# P07-LCD.net
KiCad netlist of a schematic drawn in Altium Designer
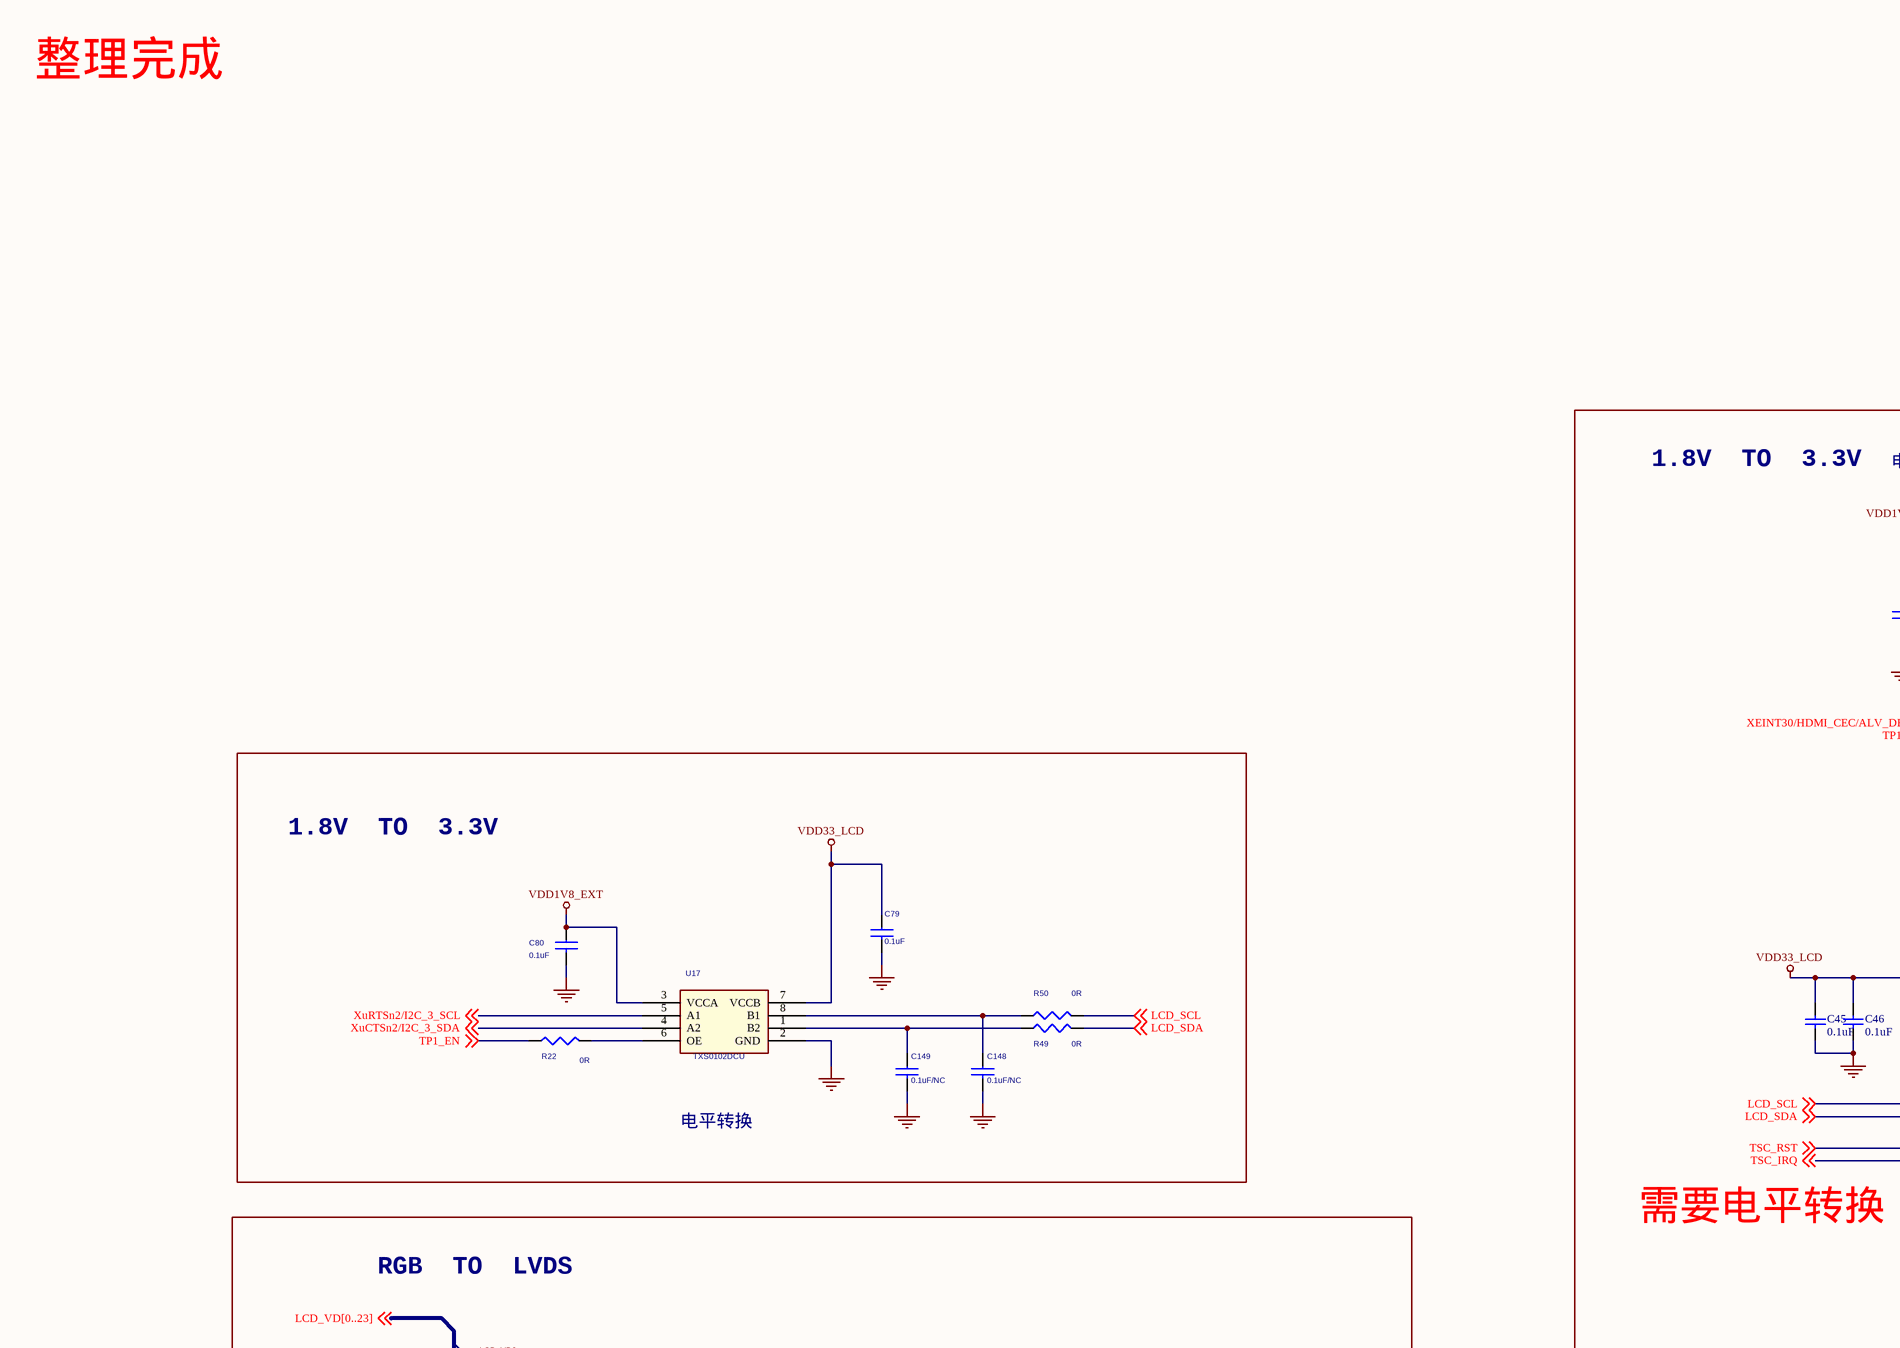
[diagram p0: P07-LCD.SchDoc, top left]
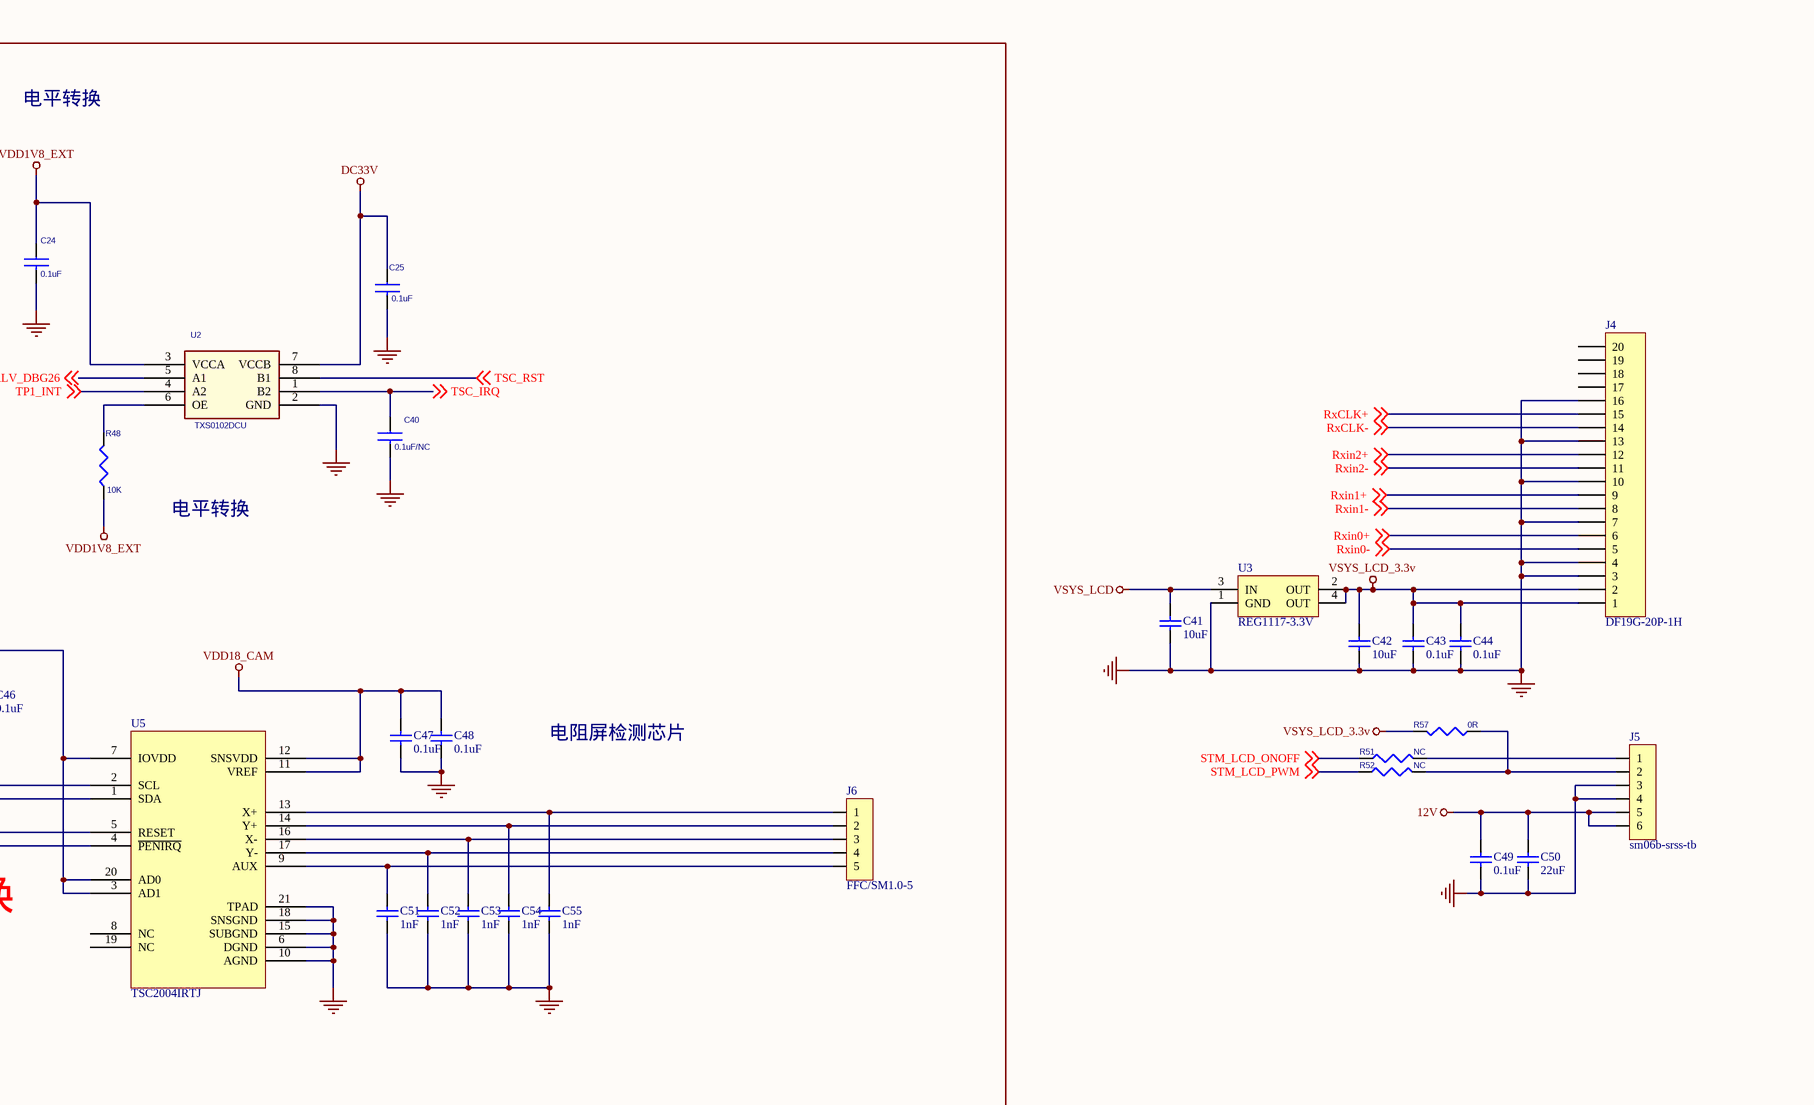
[diagram p1: P07-LCD.SchDoc, top right]
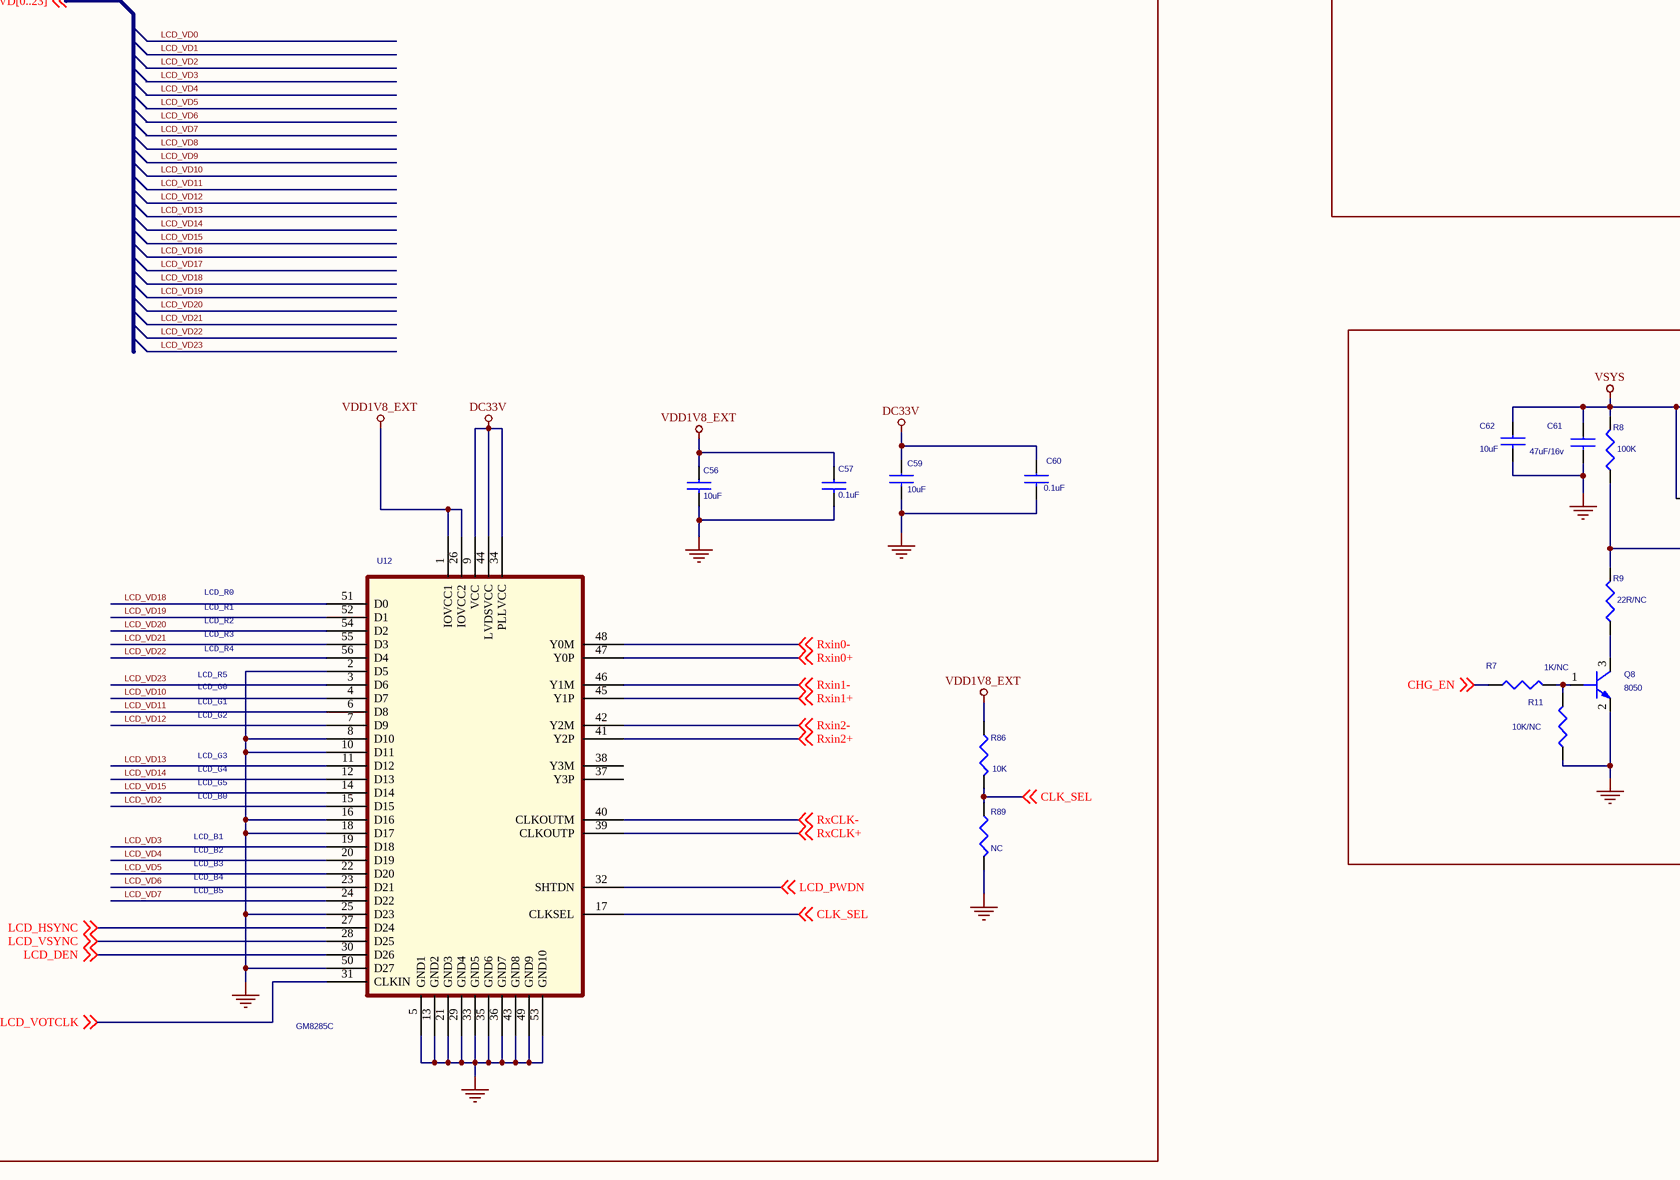
[diagram p2: P07-LCD.SchDoc, bottom left]
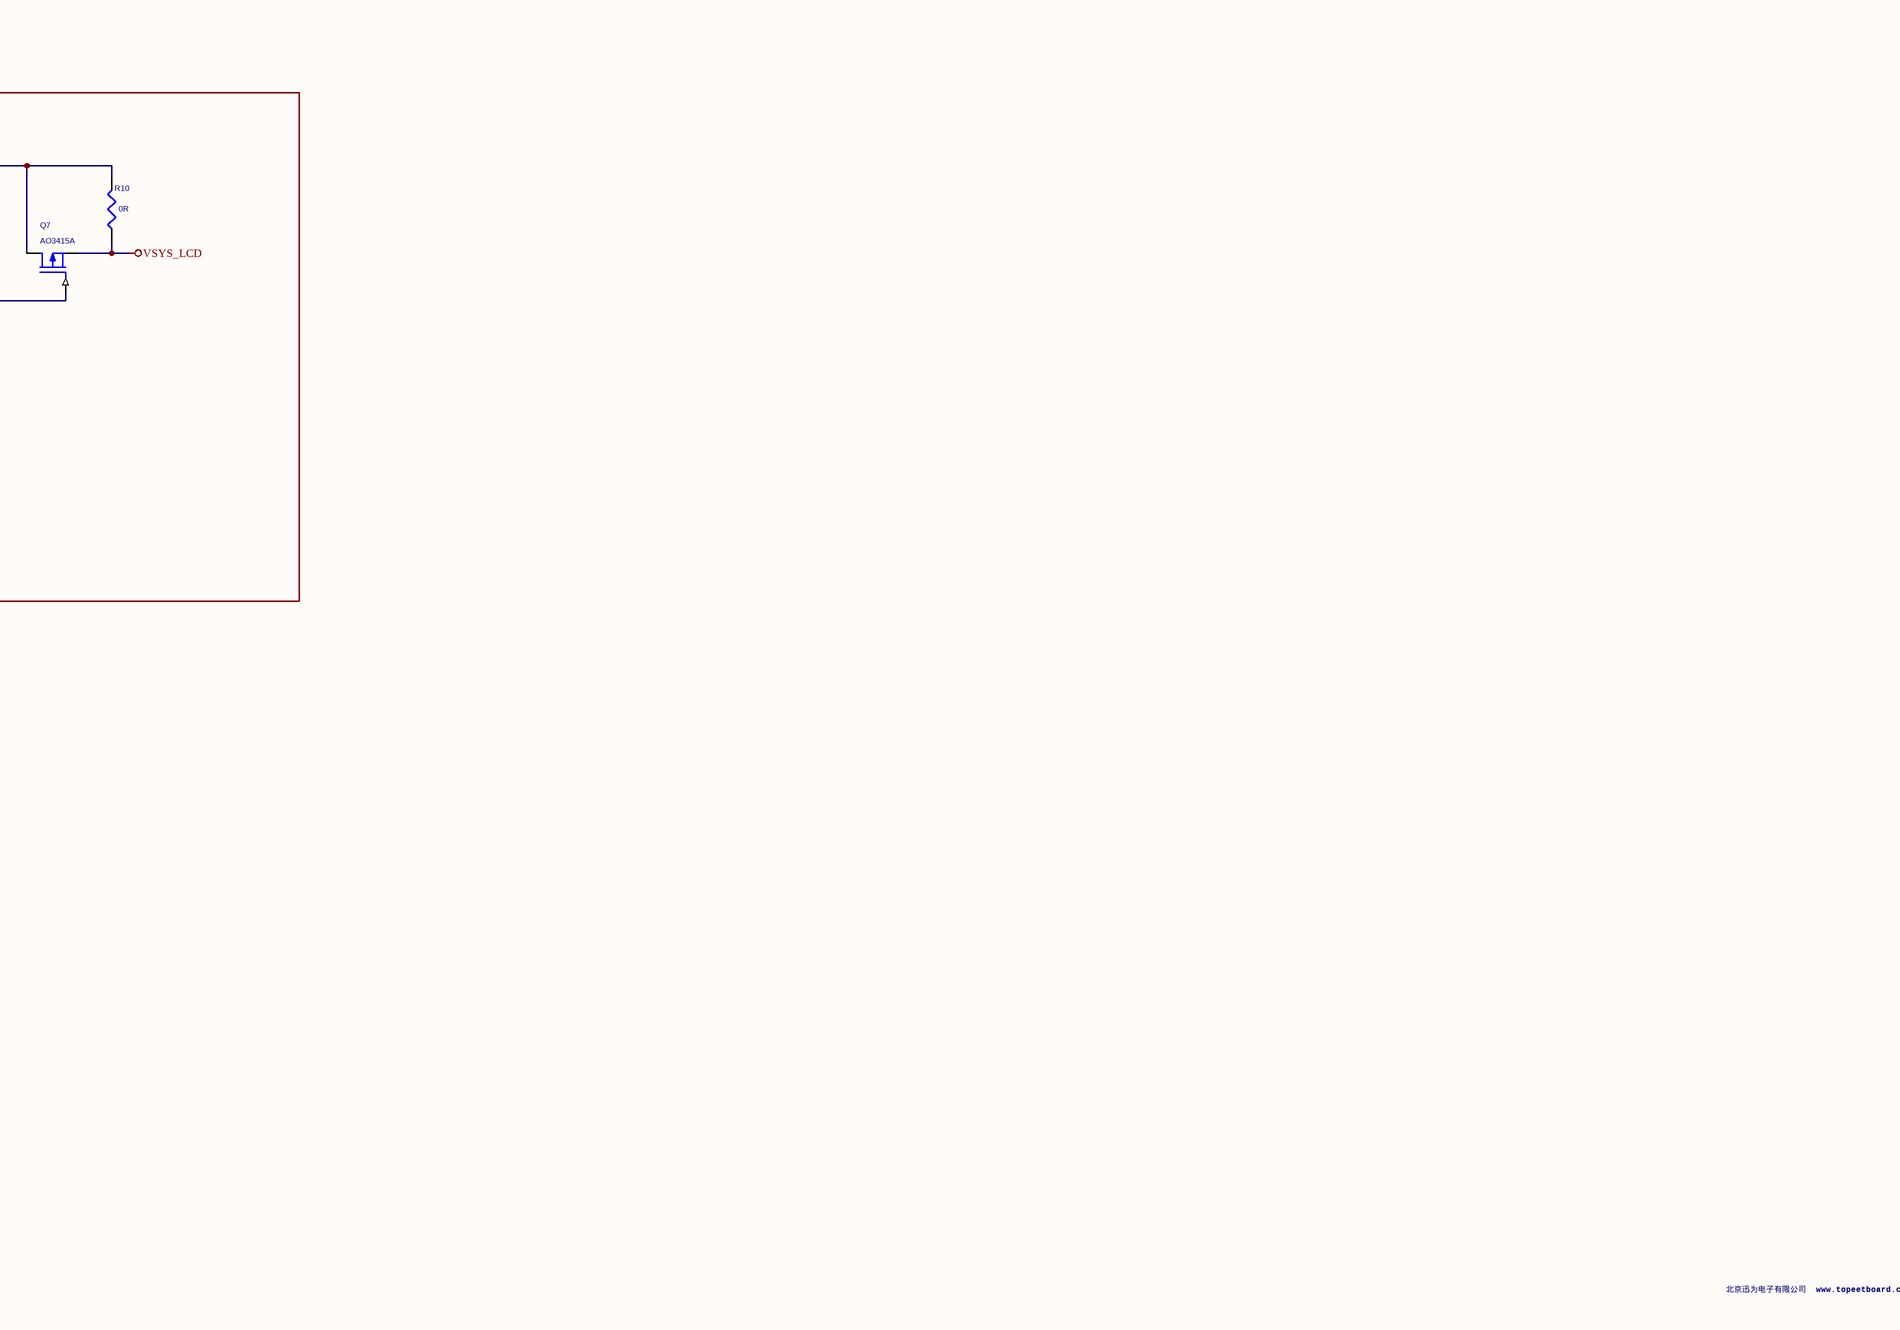
[diagram p3: P07-LCD.SchDoc, bottom right]

(export (version "E")
  (design (tool "Eeschema 10.0.6"))
  (components
    (comp (ref "C24") (value "0.1uF") (footprint "C0603-S") (libsource (lib "*") (part "C0603_0")))
    (comp (ref "C25") (value "0.1uF") (footprint "C0603-S") (libsource (lib "*") (part "C0603_0")))
    (comp (ref "C40") (value "0.1uF/NC") (footprint "C0603-S") (libsource (lib "*") (part "C0603_0")))
    (comp (ref "C41")
      (value "10uF")
      (footprint "C0603-s")
      (description "CAP")
      (fields (field (name "PUBLISHER") "Altium Limited"))
      (libsource (lib "Passive Components Class") (part "CAP"))
    )
    (comp (ref "C42")
      (value "10uF")
      (footprint "C0603-s")
      (description "CAP")
      (fields (field (name "PUBLISHER") "Altium Limited"))
      (libsource (lib "Passive Components Class") (part "CAP"))
    )
    (comp (ref "C43")
      (value "0.1uF")
      (footprint "C0603-s")
      (description "CAP")
      (fields (field (name "PUBLISHER") "Altium Limited"))
      (libsource (lib "Passive Components Class") (part "CAP"))
    )
    (comp (ref "C44")
      (value "0.1uF")
      (footprint "C0603-s")
      (description "CAP")
      (fields (field (name "PUBLISHER") "Altium Limited"))
      (libsource (lib "Passive Components Class") (part "CAP"))
    )
    (comp (ref "C45") (value "0.1uF") (footprint "C0603-S") (libsource (lib "RLCYDF") (part "Cap Semi")))
    (comp (ref "C46") (value "0.1uF") (footprint "C0603-S") (libsource (lib "RLCYDF") (part "Cap Semi")))
    (comp (ref "C47") (value "0.1uF") (footprint "C0603-S") (libsource (lib "RLCYDF") (part "Cap Semi")))
    (comp (ref "C48") (value "0.1uF") (footprint "C0603-S") (libsource (lib "RLCYDF") (part "Cap Semi")))
    (comp (ref "C49")
      (value "0.1uF")
      (footprint "C0603-s")
      (description "CAP")
      (fields (field (name "PUBLISHER") "Altium Limited"))
      (libsource (lib "Passive Components Class") (part "CAP"))
    )
    (comp (ref "C50")
      (value "22uF")
      (footprint "C0805-s")
      (description "CAP")
      (fields (field (name "PUBLISHER") "Altium Limited"))
      (libsource (lib "Passive Components Class") (part "CAP"))
    )
    (comp (ref "C51") (value "1nF") (footprint "C0603-S") (libsource (lib "RLCYDF") (part "Cap Semi")))
    (comp (ref "C52") (value "1nF") (footprint "C0603-S") (libsource (lib "RLCYDF") (part "Cap Semi")))
    (comp (ref "C53") (value "1nF") (footprint "C0603-S") (libsource (lib "RLCYDF") (part "Cap Semi")))
    (comp (ref "C54") (value "1nF") (footprint "C0603-S") (libsource (lib "RLCYDF") (part "Cap Semi")))
    (comp (ref "C55") (value "1nF") (footprint "C0603-S") (libsource (lib "RLCYDF") (part "Cap Semi")))
    (comp (ref "C56") (value "10uF") (footprint "C0805-S") (libsource (lib "*") (part "C1608_Dup2")))
    (comp (ref "C57") (value "0.1uF") (footprint "C0603-S") (libsource (lib "*") (part "C0402_0")))
    (comp (ref "C59") (value "10uF") (footprint "C0805-S") (libsource (lib "*") (part "C1608_Dup2")))
    (comp (ref "C60") (value "0.1uF") (footprint "C0603-S") (libsource (lib "*") (part "C0402_0")))
    (comp (ref "C61") (value "47uF/16v") (footprint "C1206-S") (libsource (lib "*") (part "C1608_Dup2")))
    (comp (ref "C62") (value "10uF") (footprint "C0805-S") (libsource (lib "*") (part "C1608_Dup2")))
    (comp (ref "C79") (value "0.1uF") (footprint "C0603-S") (libsource (lib "*") (part "C0603_0")))
    (comp (ref "C80") (value "0.1uF") (footprint "C0603-S") (libsource (lib "*") (part "C0603_0")))
    (comp (ref "C148") (value "0.1uF/NC") (footprint "C0603-S") (libsource (lib "*") (part "C0402_0")))
    (comp (ref "C149") (value "0.1uF/NC") (footprint "C0603-S") (libsource (lib "*") (part "C0402_0")))
    (comp (ref "J4")
      (value "DF19G-20P-1H")
      (footprint "DF19G-20P-1H")
      (description "Header, 20-Pin")
      (fields (field (name "PUBLISHER") "Altium Limited"))
      (libsource (lib "Miscellaneous Connectors") (part "Header 20"))
    )
    (comp (ref "J5")
      (value "sm06b-srss-tb")
      (footprint "sm06b-srss-tb")
      (libsource (lib "Connector Class") (part "HEADER1X6"))
    )
    (comp (ref "J6")
      (value "FFC/SM1.0-5")
      (footprint "FFC/SM1.0-5")
      (libsource (lib "Connector Class") (part "HEADER1X5"))
    )
    (comp (ref "Q7") (value "AO3415A") (libsource (lib "*") (part "MOSFET P")))
    (comp (ref "Q8") (value "8050") (libsource (lib "*") (part "L14P2/TO_1")))
    (comp (ref "R7") (value "1K/NC") (footprint "R0603-S") (libsource (lib "*") (part "R1005_0_Dup1")))
    (comp (ref "R8") (value "100K") (footprint "R0603-S") (libsource (lib "*") (part "R1005_0_Dup1")))
    (comp (ref "R9") (value "22R/NC") (footprint "R0603-S") (libsource (lib "*") (part "R1005_0_Dup1")))
    (comp (ref "R10") (value "0R") (footprint "R0603-S") (libsource (lib "*") (part "R1005_0_Dup1")))
    (comp (ref "R11") (value "10K/NC") (footprint "R0603-S") (libsource (lib "*") (part "R1005_0_Dup1")))
    (comp (ref "R22") (value "0R") (footprint "R0603-S") (libsource (lib "*") (part "R1005_0_Dup1")))
    (comp (ref "R48") (value "10K") (footprint "R0603-S") (libsource (lib "*") (part "R0603_0")))
    (comp (ref "R49") (value "0R") (footprint "R0603-S") (libsource (lib "*") (part "R1005_0_Dup1")))
    (comp (ref "R50") (value "0R") (footprint "R0603-S") (libsource (lib "*") (part "R1005_0_Dup1")))
    (comp (ref "R51") (value "NC") (footprint "R0603-S") (libsource (lib "*") (part "R1005_0_Dup1")))
    (comp (ref "R52") (value "NC") (footprint "R0603-S") (libsource (lib "*") (part "R1005_0_Dup1")))
    (comp (ref "R57") (value "0R") (footprint "R0603-S") (libsource (lib "*") (part "R0603_0")))
    (comp (ref "R86") (value "10K") (footprint "R0603-S") (libsource (lib "*") (part "R1005_0_Dup1")))
    (comp (ref "R89") (value "NC") (footprint "R0603-S") (libsource (lib "*") (part "R1005_0_Dup1")))
    (comp (ref "U2") (value "TXS0102DCU") (libsource (lib "*") (part "TXS0102DCU_1")))
    (comp (ref "U3")
      (value "REG1117-3.3V")
      (footprint "SOT-223")
      (description "800mA and 1A Low Dropout Positive Regulator 2.85V, 3.3V, 5V, and Adjustable")
      (fields (field (name "PUBLISHER") "Altium Limited"))
      (libsource (lib "BB Power Mgt Voltage Regulator") (part "REG1117-3.3"))
    )
    (comp (ref "U5")
      (value "TSC2004IRTJ")
      (footprint "QFN20")
      (description "Current Sensor")
      (libsource (lib "Sensor Class") (part "TSC2004IRTJ"))
    )
    (comp (ref "U12")
      (value "GM8285C")
      (footprint "TSSOP56")
      (libsource (lib "*") (part "U-SN75LVDS83BDGG_3"))
    )
    (comp (ref "U17") (value "TXS0102DCU") (libsource (lib "*") (part "TXS0102DCU_1")))
  )
  (nets
    (net (code "1") (name "12V") (class "Default")
      (node (ref "C49") (pin "2") (pinfunction "2_2") (pintype "passive"))
      (node (ref "C50") (pin "2") (pinfunction "2_2") (pintype "passive"))
      (node (ref "J5") (pin "5") (pinfunction "5_5") (pintype "passive"))
      (node (ref "J5") (pin "6") (pinfunction "6_6") (pintype "passive"))
    )
    (net (code "2") (name "CHG_EN") (class "Default")
      (node (ref "R7") (pin "2") (pinfunction "2_2") (pintype "passive"))
    )
    (net (code "3") (name "CLK_SEL") (class "Default")
      (node (ref "R86") (pin "2") (pinfunction "2_2") (pintype "passive"))
      (node (ref "R89") (pin "1") (pinfunction "1_1") (pintype "passive"))
      (node (ref "U12") (pin "17") (pinfunction "CLKSEL_17") (pintype "passive"))
    )
    (net (code "4") (name "DC33V") (class "Default")
      (node (ref "C25") (pin "1") (pinfunction "1_1") (pintype "passive"))
      (node (ref "C59") (pin "1") (pinfunction "1_1") (pintype "passive"))
      (node (ref "C60") (pin "1") (pinfunction "1_1") (pintype "passive"))
      (node (ref "U12") (pin "34") (pinfunction "PLLVCC_34") (pintype "passive"))
      (node (ref "U12") (pin "44") (pinfunction "LVDSVCC_44") (pintype "passive"))
      (node (ref "U12") (pin "9") (pinfunction "VCC_9") (pintype "passive"))
      (node (ref "U2") (pin "7") (pinfunction "VCCB_7") (pintype "passive"))
    )
    (net (code "5") (name "GND") (class "Default")
      (node (ref "C148") (pin "2") (pinfunction "2_2") (pintype "passive"))
      (node (ref "C149") (pin "2") (pinfunction "2_2") (pintype "passive"))
      (node (ref "C24") (pin "2") (pinfunction "2_2") (pintype "passive"))
      (node (ref "C25") (pin "2") (pinfunction "2_2") (pintype "passive"))
      (node (ref "C40") (pin "2") (pinfunction "2_2") (pintype "passive"))
      (node (ref "C41") (pin "1") (pinfunction "1_1") (pintype "passive"))
      (node (ref "C42") (pin "1") (pinfunction "1_1") (pintype "passive"))
      (node (ref "C43") (pin "1") (pinfunction "1_1") (pintype "passive"))
      (node (ref "C44") (pin "1") (pinfunction "1_1") (pintype "passive"))
      (node (ref "C45") (pin "1") (pinfunction "1_1") (pintype "passive"))
      (node (ref "C46") (pin "1") (pinfunction "1_1") (pintype "passive"))
      (node (ref "C47") (pin "1") (pinfunction "1_1") (pintype "passive"))
      (node (ref "C48") (pin "1") (pinfunction "1_1") (pintype "passive"))
      (node (ref "C49") (pin "1") (pinfunction "1_1") (pintype "passive"))
      (node (ref "C50") (pin "1") (pinfunction "1_1") (pintype "passive"))
      (node (ref "C51") (pin "1") (pinfunction "1_1") (pintype "passive"))
      (node (ref "C52") (pin "1") (pinfunction "1_1") (pintype "passive"))
      (node (ref "C53") (pin "1") (pinfunction "1_1") (pintype "passive"))
      (node (ref "C54") (pin "1") (pinfunction "1_1") (pintype "passive"))
      (node (ref "C55") (pin "1") (pinfunction "1_1") (pintype "passive"))
      (node (ref "C56") (pin "2") (pinfunction "2_2") (pintype "passive"))
      (node (ref "C57") (pin "2") (pinfunction "2_2") (pintype "passive"))
      (node (ref "C59") (pin "2") (pinfunction "2_2") (pintype "passive"))
      (node (ref "C60") (pin "2") (pinfunction "2_2") (pintype "passive"))
      (node (ref "C61") (pin "2") (pinfunction "2_2") (pintype "passive"))
      (node (ref "C62") (pin "2") (pinfunction "2_2") (pintype "passive"))
      (node (ref "C79") (pin "2") (pinfunction "2_2") (pintype "passive"))
      (node (ref "C80") (pin "2") (pinfunction "2_2") (pintype "passive"))
      (node (ref "J4") (pin "10") (pinfunction "10_10") (pintype "passive"))
      (node (ref "J4") (pin "13") (pinfunction "13_13") (pintype "passive"))
      (node (ref "J4") (pin "16") (pinfunction "16_16") (pintype "passive"))
      (node (ref "J4") (pin "3") (pinfunction "3_3") (pintype "passive"))
      (node (ref "J4") (pin "4") (pinfunction "4_4") (pintype "passive"))
      (node (ref "J4") (pin "7") (pinfunction "7_7") (pintype "passive"))
      (node (ref "J5") (pin "3") (pinfunction "3_3") (pintype "passive"))
      (node (ref "J5") (pin "4") (pinfunction "4_4") (pintype "passive"))
      (node (ref "Q8") (pin "2") (pinfunction "EMITTER_2") (pintype "passive"))
      (node (ref "R11") (pin "2") (pinfunction "2_2") (pintype "passive"))
      (node (ref "R89") (pin "2") (pinfunction "2_2") (pintype "passive"))
      (node (ref "U12") (pin "10") (pinfunction "D11_10") (pintype "passive"))
      (node (ref "U12") (pin "13") (pinfunction "GND2_13") (pintype "passive"))
      (node (ref "U12") (pin "16") (pinfunction "D16_16") (pintype "passive"))
      (node (ref "U12") (pin "18") (pinfunction "D17_18") (pintype "passive"))
      (node (ref "U12") (pin "2") (pinfunction "D5_2") (pintype "passive"))
      (node (ref "U12") (pin "21") (pinfunction "GND3_21") (pintype "passive"))
      (node (ref "U12") (pin "25") (pinfunction "D23_25") (pintype "passive"))
      (node (ref "U12") (pin "29") (pinfunction "GND4_29") (pintype "passive"))
      (node (ref "U12") (pin "33") (pinfunction "GND5_33") (pintype "passive"))
      (node (ref "U12") (pin "35") (pinfunction "GND6_35") (pintype "passive"))
      (node (ref "U12") (pin "36") (pinfunction "GND7_36") (pintype "passive"))
      (node (ref "U12") (pin "43") (pinfunction "GND8_43") (pintype "passive"))
      (node (ref "U12") (pin "49") (pinfunction "GND9_49") (pintype "passive"))
      (node (ref "U12") (pin "5") (pinfunction "GND1_5") (pintype "passive"))
      (node (ref "U12") (pin "50") (pinfunction "D27_50") (pintype "passive"))
      (node (ref "U12") (pin "53") (pinfunction "GND10_53") (pintype "passive"))
      (node (ref "U12") (pin "8") (pinfunction "D10_8") (pintype "passive"))
      (node (ref "U17") (pin "2") (pinfunction "GND_2") (pintype "passive"))
      (node (ref "U2") (pin "2") (pinfunction "GND_2") (pintype "passive"))
      (node (ref "U3") (pin "1") (pinfunction "GND_1") (pintype "power_in"))
      (node (ref "U5") (pin "10") (pinfunction "AGND_10") (pintype "passive"))
      (node (ref "U5") (pin "15") (pinfunction "SUBGND_15") (pintype "passive"))
      (node (ref "U5") (pin "18") (pinfunction "SNSGND_18") (pintype "passive"))
      (node (ref "U5") (pin "21") (pinfunction "TPAD_21") (pintype "passive"))
      (node (ref "U5") (pin "6") (pinfunction "DGND_6") (pintype "passive"))
    )
    (net (code "6") (name "LCD_DEN") (class "Default")
      (node (ref "U12") (pin "30") (pinfunction "D26_30") (pintype "passive"))
    )
    (net (code "7") (name "LCD_HSYNC") (class "Default")
      (node (ref "U12") (pin "27") (pinfunction "D24_27") (pintype "passive"))
    )
    (net (code "8") (name "LCD_PWDN") (class "Default")
      (node (ref "U12") (pin "32") (pinfunction "SHTDN_32") (pintype "passive"))
    )
    (net (code "9") (name "LCD_SCL") (class "Default")
      (node (ref "R50") (pin "2") (pinfunction "2_2") (pintype "passive"))
      (node (ref "U5") (pin "2") (pinfunction "SCL_2") (pintype "passive"))
    )
    (net (code "10") (name "LCD_SDA") (class "Default")
      (node (ref "R49") (pin "2") (pinfunction "2_2") (pintype "passive"))
      (node (ref "U5") (pin "1") (pinfunction "SDA_1") (pintype "passive"))
    )
    (net (code "13") (name "LCD_VD2") (class "Default")
      (node (ref "U12") (pin "15") (pinfunction "D15_15") (pintype "passive"))
    )
    (net (code "14") (name "LCD_VD3") (class "Default")
      (node (ref "U12") (pin "19") (pinfunction "D18_19") (pintype "passive"))
    )
    (net (code "15") (name "LCD_VD4") (class "Default")
      (node (ref "U12") (pin "20") (pinfunction "D19_20") (pintype "passive"))
    )
    (net (code "16") (name "LCD_VD5") (class "Default")
      (node (ref "U12") (pin "22") (pinfunction "D20_22") (pintype "passive"))
    )
    (net (code "17") (name "LCD_VD6") (class "Default")
      (node (ref "U12") (pin "23") (pinfunction "D21_23") (pintype "passive"))
    )
    (net (code "18") (name "LCD_VD7") (class "Default")
      (node (ref "U12") (pin "24") (pinfunction "D22_24") (pintype "passive"))
    )
    (net (code "21") (name "LCD_VD10") (class "Default")
      (node (ref "U12") (pin "4") (pinfunction "D7_4") (pintype "passive"))
    )
    (net (code "22") (name "LCD_VD11") (class "Default")
      (node (ref "U12") (pin "6") (pinfunction "D8_6") (pintype "passive"))
    )
    (net (code "23") (name "LCD_VD12") (class "Default")
      (node (ref "U12") (pin "7") (pinfunction "D9_7") (pintype "passive"))
    )
    (net (code "24") (name "LCD_VD13") (class "Default")
      (node (ref "U12") (pin "11") (pinfunction "D12_11") (pintype "passive"))
    )
    (net (code "25") (name "LCD_VD14") (class "Default")
      (node (ref "U12") (pin "12") (pinfunction "D13_12") (pintype "passive"))
    )
    (net (code "26") (name "LCD_VD15") (class "Default")
      (node (ref "U12") (pin "14") (pinfunction "D14_14") (pintype "passive"))
    )
    (net (code "29") (name "LCD_VD18") (class "Default")
      (node (ref "U12") (pin "51") (pinfunction "D0_51") (pintype "passive"))
    )
    (net (code "30") (name "LCD_VD19") (class "Default")
      (node (ref "U12") (pin "52") (pinfunction "D1_52") (pintype "passive"))
    )
    (net (code "31") (name "LCD_VD20") (class "Default")
      (node (ref "U12") (pin "54") (pinfunction "D2_54") (pintype "passive"))
    )
    (net (code "32") (name "LCD_VD21") (class "Default")
      (node (ref "U12") (pin "55") (pinfunction "D3_55") (pintype "passive"))
    )
    (net (code "33") (name "LCD_VD22") (class "Default")
      (node (ref "U12") (pin "56") (pinfunction "D4_56") (pintype "passive"))
    )
    (net (code "34") (name "LCD_VD23") (class "Default")
      (node (ref "U12") (pin "3") (pinfunction "D6_3") (pintype "passive"))
    )
    (net (code "36") (name "LCD_VOTCLK") (class "Default")
      (node (ref "U12") (pin "31") (pinfunction "CLKIN_31") (pintype "passive"))
    )
    (net (code "37") (name "LCD_VSYNC") (class "Default")
      (node (ref "U12") (pin "28") (pinfunction "D25_28") (pintype "passive"))
    )
    (net (code "38") (name "Net-(J5-Pad1)") (class "Default")
      (node (ref "J5") (pin "1") (pinfunction "1_1") (pintype "passive"))
      (node (ref "R51") (pin "2") (pinfunction "2_2") (pintype "passive"))
    )
    (net (code "39") (name "Net-(J5-Pad2)") (class "Default")
      (node (ref "J5") (pin "2") (pinfunction "2_2") (pintype "passive"))
      (node (ref "R52") (pin "2") (pinfunction "2_2") (pintype "passive"))
      (node (ref "R57") (pin "1") (pinfunction "1_1") (pintype "passive"))
    )
    (net (code "40") (name "Net-(Q7-GATE)") (class "Default")
      (node (ref "Q7") (pin "1") (pinfunction "GATE_1") (pintype "input"))
      (node (ref "R8") (pin "2") (pinfunction "2_2") (pintype "passive"))
      (node (ref "R9") (pin "1") (pinfunction "1_1") (pintype "passive"))
    )
    (net (code "41") (name "Net-(Q8-BASE)") (class "Default")
      (node (ref "Q8") (pin "1") (pinfunction "BASE_1") (pintype "passive"))
      (node (ref "R11") (pin "1") (pinfunction "1_1") (pintype "passive"))
      (node (ref "R7") (pin "1") (pinfunction "1_1") (pintype "passive"))
    )
    (net (code "42") (name "Net-(Q8-COLLECTOR)") (class "Default")
      (node (ref "Q8") (pin "3") (pinfunction "COLLECTOR_3") (pintype "passive"))
      (node (ref "R9") (pin "2") (pinfunction "2_2") (pintype "passive"))
    )
    (net (code "43") (name "Net-(U2-OE)") (class "Default")
      (node (ref "R48") (pin "2") (pinfunction "2_2") (pintype "passive"))
      (node (ref "U2") (pin "6") (pinfunction "OE_6") (pintype "passive"))
    )
    (net (code "44") (name "Net-(U5-AUX)") (class "Default")
      (node (ref "C51") (pin "2") (pinfunction "2_2") (pintype "passive"))
      (node (ref "J6") (pin "5") (pinfunction "5_5") (pintype "passive"))
      (node (ref "U5") (pin "9") (pinfunction "AUX_9") (pintype "passive"))
    )
    (net (code "45") (name "Net-(U5-X+)") (class "Default")
      (node (ref "C55") (pin "2") (pinfunction "2_2") (pintype "passive"))
      (node (ref "J6") (pin "1") (pinfunction "1_1") (pintype "passive"))
      (node (ref "U5") (pin "13") (pinfunction "X+_13") (pintype "passive"))
    )
    (net (code "46") (name "Net-(U5-X-)") (class "Default")
      (node (ref "C53") (pin "2") (pinfunction "2_2") (pintype "passive"))
      (node (ref "J6") (pin "3") (pinfunction "3_3") (pintype "passive"))
      (node (ref "U5") (pin "16") (pinfunction "X-_16") (pintype "passive"))
    )
    (net (code "47") (name "Net-(U5-Y+)") (class "Default")
      (node (ref "C54") (pin "2") (pinfunction "2_2") (pintype "passive"))
      (node (ref "J6") (pin "2") (pinfunction "2_2") (pintype "passive"))
      (node (ref "U5") (pin "14") (pinfunction "Y+_14") (pintype "passive"))
    )
    (net (code "48") (name "Net-(U5-Y-)") (class "Default")
      (node (ref "C52") (pin "2") (pinfunction "2_2") (pintype "passive"))
      (node (ref "J6") (pin "4") (pinfunction "4_4") (pintype "passive"))
      (node (ref "U5") (pin "17") (pinfunction "Y-_17") (pintype "passive"))
    )
    (net (code "49") (name "Net-(U17-B1)") (class "Default")
      (node (ref "C148") (pin "1") (pinfunction "1_1") (pintype "passive"))
      (node (ref "R50") (pin "1") (pinfunction "1_1") (pintype "passive"))
      (node (ref "U17") (pin "8") (pinfunction "B1_8") (pintype "passive"))
    )
    (net (code "50") (name "Net-(U17-B2)") (class "Default")
      (node (ref "C149") (pin "1") (pinfunction "1_1") (pintype "passive"))
      (node (ref "R49") (pin "1") (pinfunction "1_1") (pintype "passive"))
      (node (ref "U17") (pin "1") (pinfunction "B2_1") (pintype "passive"))
    )
    (net (code "51") (name "Net-(U17-OE)") (class "Default")
      (node (ref "R22") (pin "2") (pinfunction "2_2") (pintype "passive"))
      (node (ref "U17") (pin "6") (pinfunction "OE_6") (pintype "passive"))
    )
    (net (code "52") (name "RxCLK+") (class "Default")
      (node (ref "J4") (pin "15") (pinfunction "15_15") (pintype "passive"))
      (node (ref "U12") (pin "39") (pinfunction "CLKOUTP_39") (pintype "passive"))
    )
    (net (code "53") (name "RxCLK-") (class "Default")
      (node (ref "J4") (pin "14") (pinfunction "14_14") (pintype "passive"))
      (node (ref "U12") (pin "40") (pinfunction "CLKOUTM_40") (pintype "passive"))
    )
    (net (code "54") (name "Rxin0+") (class "Default")
      (node (ref "J4") (pin "6") (pinfunction "6_6") (pintype "passive"))
      (node (ref "U12") (pin "47") (pinfunction "Y0P_47") (pintype "passive"))
    )
    (net (code "55") (name "Rxin0-") (class "Default")
      (node (ref "J4") (pin "5") (pinfunction "5_5") (pintype "passive"))
      (node (ref "U12") (pin "48") (pinfunction "Y0M_48") (pintype "passive"))
    )
    (net (code "56") (name "Rxin1+") (class "Default")
      (node (ref "J4") (pin "9") (pinfunction "9_9") (pintype "passive"))
      (node (ref "U12") (pin "45") (pinfunction "Y1P_45") (pintype "passive"))
    )
    (net (code "57") (name "Rxin1-") (class "Default")
      (node (ref "J4") (pin "8") (pinfunction "8_8") (pintype "passive"))
      (node (ref "U12") (pin "46") (pinfunction "Y1M_46") (pintype "passive"))
    )
    (net (code "58") (name "Rxin2+") (class "Default")
      (node (ref "J4") (pin "12") (pinfunction "12_12") (pintype "passive"))
      (node (ref "U12") (pin "41") (pinfunction "Y2P_41") (pintype "passive"))
    )
    (net (code "59") (name "Rxin2-") (class "Default")
      (node (ref "J4") (pin "11") (pinfunction "11_11") (pintype "passive"))
      (node (ref "U12") (pin "42") (pinfunction "Y2M_42") (pintype "passive"))
    )
    (net (code "60") (name "STM_LCD_ONOFF") (class "Default")
      (node (ref "R51") (pin "1") (pinfunction "1_1") (pintype "passive"))
    )
    (net (code "61") (name "STM_LCD_PWM") (class "Default")
      (node (ref "R52") (pin "1") (pinfunction "1_1") (pintype "passive"))
    )
    (net (code "62") (name "TP1_EN") (class "Default")
      (node (ref "R22") (pin "1") (pinfunction "1_1") (pintype "passive"))
    )
    (net (code "63") (name "TP1_INT") (class "Default")
      (node (ref "U2") (pin "4") (pinfunction "A2_4") (pintype "passive"))
    )
    (net (code "64") (name "TSC_IRQ") (class "Default")
      (node (ref "C40") (pin "1") (pinfunction "1_1") (pintype "passive"))
      (node (ref "U2") (pin "1") (pinfunction "B2_1") (pintype "passive"))
      (node (ref "U5") (pin "4") (pinfunction "~{PENIRQ}_4") (pintype "passive"))
    )
    (net (code "65") (name "TSC_RST") (class "Default")
      (node (ref "U2") (pin "8") (pinfunction "B1_8") (pintype "passive"))
      (node (ref "U5") (pin "5") (pinfunction "RESET_5") (pintype "passive"))
    )
    (net (code "66") (name "VDD1V8_EXT") (class "Default")
      (node (ref "C24") (pin "1") (pinfunction "1_1") (pintype "passive"))
      (node (ref "C56") (pin "1") (pinfunction "1_1") (pintype "passive"))
      (node (ref "C57") (pin "1") (pinfunction "1_1") (pintype "passive"))
      (node (ref "C80") (pin "1") (pinfunction "1_1") (pintype "passive"))
      (node (ref "R48") (pin "1") (pinfunction "1_1") (pintype "passive"))
      (node (ref "R86") (pin "1") (pinfunction "1_1") (pintype "passive"))
      (node (ref "U12") (pin "1") (pinfunction "IOVCC1_1") (pintype "passive"))
      (node (ref "U12") (pin "26") (pinfunction "IOVCC2_26") (pintype "passive"))
      (node (ref "U17") (pin "3") (pinfunction "VCCA_3") (pintype "passive"))
      (node (ref "U2") (pin "3") (pinfunction "VCCA_3") (pintype "passive"))
    )
    (net (code "67") (name "VDD18_CAM") (class "Default")
      (node (ref "C47") (pin "2") (pinfunction "2_2") (pintype "passive"))
      (node (ref "C48") (pin "2") (pinfunction "2_2") (pintype "passive"))
      (node (ref "U5") (pin "11") (pinfunction "VREF_11") (pintype "passive"))
      (node (ref "U5") (pin "12") (pinfunction "SNSVDD_12") (pintype "passive"))
    )
    (net (code "68") (name "VDD33_LCD") (class "Default")
      (node (ref "C45") (pin "2") (pinfunction "2_2") (pintype "passive"))
      (node (ref "C46") (pin "2") (pinfunction "2_2") (pintype "passive"))
      (node (ref "C79") (pin "1") (pinfunction "1_1") (pintype "passive"))
      (node (ref "U17") (pin "7") (pinfunction "VCCB_7") (pintype "passive"))
      (node (ref "U5") (pin "20") (pinfunction "AD0_20") (pintype "passive"))
      (node (ref "U5") (pin "3") (pinfunction "AD1_3") (pintype "passive"))
      (node (ref "U5") (pin "7") (pinfunction "IOVDD_7") (pintype "passive"))
    )
    (net (code "69") (name "VSYS") (class "Default")
      (node (ref "C61") (pin "1") (pinfunction "1_1") (pintype "passive"))
      (node (ref "C62") (pin "1") (pinfunction "1_1") (pintype "passive"))
      (node (ref "Q7") (pin "2") (pinfunction "DRAIN_2") (pintype "passive"))
      (node (ref "R10") (pin "1") (pinfunction "1_1") (pintype "passive"))
      (node (ref "R8") (pin "1") (pinfunction "1_1") (pintype "passive"))
    )
    (net (code "70") (name "VSYS_LCD") (class "Default")
      (node (ref "C41") (pin "2") (pinfunction "2_2") (pintype "passive"))
      (node (ref "Q7") (pin "3") (pinfunction "SOURCE_3") (pintype "passive"))
      (node (ref "R10") (pin "2") (pinfunction "2_2") (pintype "passive"))
      (node (ref "U3") (pin "3") (pinfunction "IN_3") (pintype "power_in"))
    )
    (net (code "71") (name "VSYS_LCD_3.3v") (class "Default")
      (node (ref "C42") (pin "2") (pinfunction "2_2") (pintype "passive"))
      (node (ref "C43") (pin "2") (pinfunction "2_2") (pintype "passive"))
      (node (ref "C44") (pin "2") (pinfunction "2_2") (pintype "passive"))
      (node (ref "J4") (pin "1") (pinfunction "1_1") (pintype "passive"))
      (node (ref "J4") (pin "2") (pinfunction "2_2") (pintype "passive"))
      (node (ref "R57") (pin "2") (pinfunction "2_2") (pintype "passive"))
      (node (ref "U3") (pin "2") (pinfunction "OUT_2") (pintype "power_in"))
      (node (ref "U3") (pin "4") (pinfunction "OUT_4") (pintype "power_in"))
    )
    (net (code "72") (name "XEINT30{slash}HDMI_CEC{slash}ALV_DBG26") (class "Default")
      (node (ref "U2") (pin "5") (pinfunction "A1_5") (pintype "passive"))
    )
    (net (code "73") (name "XuCTSn2{slash}I2C_3_SDA") (class "Default")
      (node (ref "U17") (pin "4") (pinfunction "A2_4") (pintype "passive"))
    )
    (net (code "74") (name "XuRTSn2{slash}I2C_3_SCL") (class "Default")
      (node (ref "U17") (pin "5") (pinfunction "A1_5") (pintype "passive"))
    )
    (net (code "75") (name "unconnected-(J4-Pad17)") (class "Default")
      (node (ref "J4") (pin "17") (pinfunction "17_17") (pintype "passive"))
    )
    (net (code "76") (name "unconnected-(J4-Pad18)") (class "Default")
      (node (ref "J4") (pin "18") (pinfunction "18_18") (pintype "passive"))
    )
    (net (code "77") (name "unconnected-(J4-Pad19)") (class "Default")
      (node (ref "J4") (pin "19") (pinfunction "19_19") (pintype "passive"))
    )
    (net (code "78") (name "unconnected-(J4-Pad20)") (class "Default")
      (node (ref "J4") (pin "20") (pinfunction "20_20") (pintype "passive"))
    )
    (net (code "79") (name "unconnected-(U5-NC-Pad8)") (class "Default")
      (node (ref "U5") (pin "8") (pinfunction "NC_8") (pintype "passive"))
    )
    (net (code "80") (name "unconnected-(U5-NC-Pad19)") (class "Default")
      (node (ref "U5") (pin "19") (pinfunction "NC_19") (pintype "passive"))
    )
    (net (code "81") (name "unconnected-(U12-Y3M-Pad38)") (class "Default")
      (node (ref "U12") (pin "38") (pinfunction "Y3M_38") (pintype "passive"))
    )
    (net (code "82") (name "unconnected-(U12-Y3P-Pad37)") (class "Default")
      (node (ref "U12") (pin "37") (pinfunction "Y3P_37") (pintype "passive"))
    )
  )
)
